# amiga-usb-disk-reader.net
KiCad netlist of a schematic drawn in EAGLE
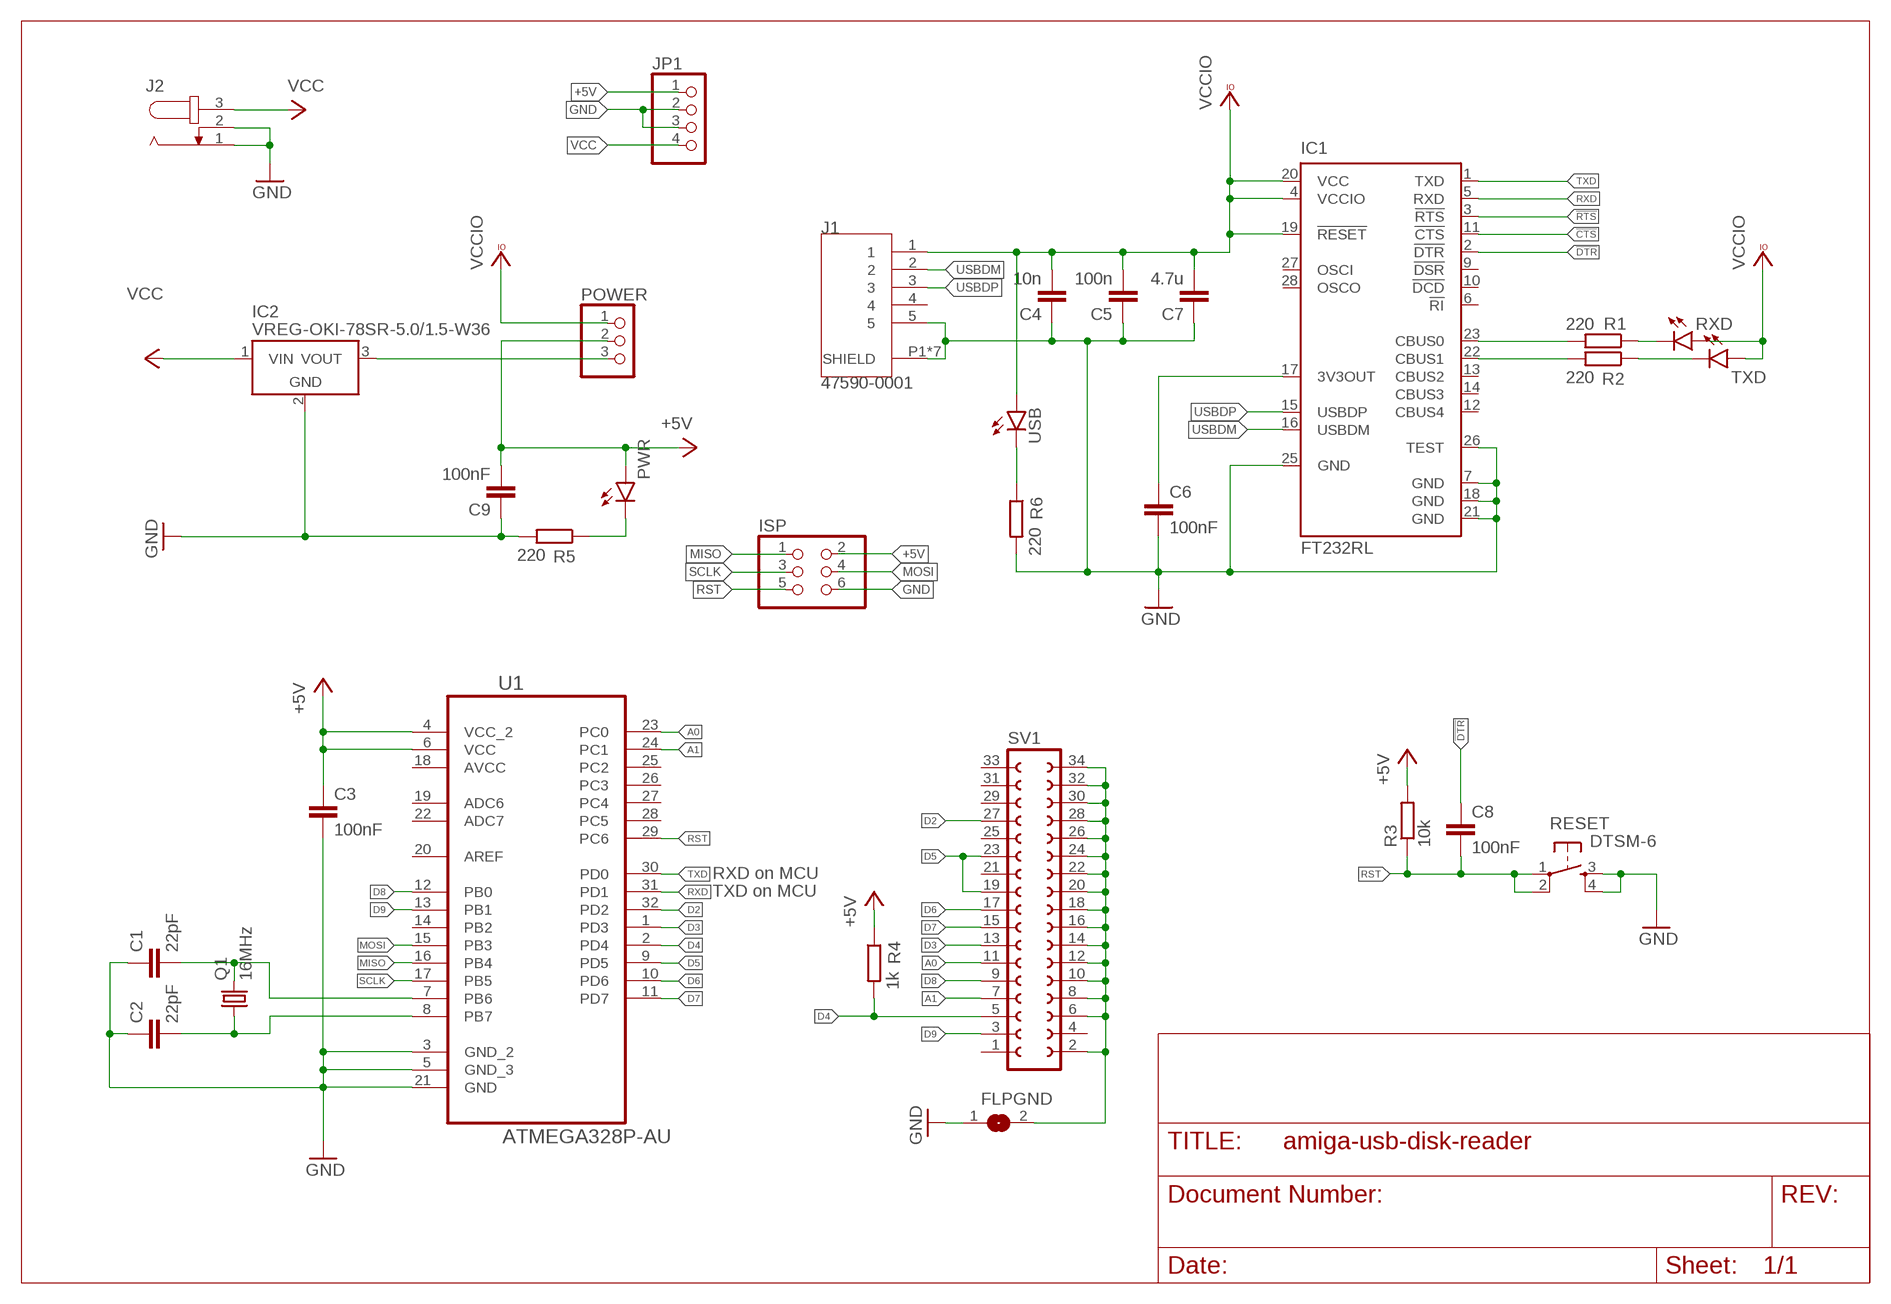
[diagram p0: schematic, sheet 1]

(export (version "E")
  (design (tool "Eeschema 10.0.6"))
  (components
    (comp (ref "C1")
      (value "22pF")
      (footprint "eagle-import:C0805")
      (libsource (lib "eagle-import") (part "C-EUC0805"))
    )
    (comp (ref "C2")
      (value "22pF")
      (footprint "eagle-import:C0805")
      (libsource (lib "eagle-import") (part "C-EUC0805"))
    )
    (comp (ref "C3")
      (value "100nF")
      (footprint "eagle-import:C0805")
      (libsource (lib "eagle-import") (part "C-EUC0805"))
    )
    (comp (ref "C4")
      (value "10n")
      (footprint "eagle-import:C0805")
      (libsource (lib "eagle-import") (part "C-EUC0805"))
    )
    (comp (ref "C5")
      (value "100n")
      (footprint "eagle-import:C0805")
      (libsource (lib "eagle-import") (part "C-EUC0805"))
    )
    (comp (ref "C6")
      (value "100nF")
      (footprint "eagle-import:C0805")
      (libsource (lib "eagle-import") (part "C-EUC0805"))
    )
    (comp (ref "C7")
      (value "4.7u")
      (footprint "eagle-import:C0805")
      (libsource (lib "eagle-import") (part "C-EUC0805"))
    )
    (comp (ref "C8")
      (value "100nF")
      (footprint "eagle-import:C0805")
      (libsource (lib "eagle-import") (part "C-EUC0805"))
    )
    (comp (ref "C9")
      (value "100nF")
      (footprint "eagle-import:C0805")
      (libsource (lib "eagle-import") (part "C-EUC0805"))
    )
    (comp (ref "FLPGND")
      (value "SJ")
      (footprint "eagle-import:SJ")
      (libsource (lib "eagle-import") (part "SJ"))
    )
    (comp (ref "IC1")
      (value "FT232RL")
      (footprint "eagle-import:SSOP28")
      (libsource (lib "eagle-import") (part "FT232RL"))
    )
    (comp (ref "IC2")
      (value "VREG-OKI-78SR-5.0/1.5-W36")
      (footprint "eagle-import:OKI-78SR")
      (libsource (lib "eagle-import") (part "VREG-OKI-78SR-5.0/1.5-W36"))
    )
    (comp (ref "ISP")
      (value "PINHD-2X3")
      (footprint "eagle-import:2X03")
      (libsource (lib "eagle-import") (part "PINHD-2X3"))
    )
    (comp (ref "J1")
      (value "47590-0001")
      (footprint "eagle-import:MOLEX_47590-0001")
      (fields (field (name "MF") "Molex"))
      (libsource (lib "eagle-import") (part "47590-0001"))
    )
    (comp (ref "J2")
      (value "JACK-PLUG0")
      (footprint "eagle-import:SPC4077")
      (libsource (lib "eagle-import") (part "JACK-PLUG0"))
    )
    (comp (ref "JP1")
      (value "PINHD-1X4")
      (footprint "eagle-import:1X04")
      (libsource (lib "eagle-import") (part "PINHD-1X4"))
    )
    (comp (ref "POWER")
      (value "PINHD-1X3")
      (footprint "eagle-import:1X03")
      (libsource (lib "eagle-import") (part "PINHD-1X3"))
    )
    (comp (ref "PWR")
      (value "LEDSML0805")
      (footprint "eagle-import:SML0805")
      (libsource (lib "eagle-import") (part "LEDSML0805"))
    )
    (comp (ref "Q1")
      (value "16MHz")
      (footprint "eagle-import:HC49U70")
      (libsource (lib "eagle-import") (part "CRYSTALHC49U70"))
    )
    (comp (ref "R1")
      (value "220")
      (footprint "eagle-import:R0805")
      (libsource (lib "eagle-import") (part "R-EU_R0805"))
    )
    (comp (ref "R2")
      (value "220")
      (footprint "eagle-import:R0805")
      (libsource (lib "eagle-import") (part "R-EU_R0805"))
    )
    (comp (ref "R3")
      (value "10k")
      (footprint "eagle-import:R0805")
      (libsource (lib "eagle-import") (part "R-EU_R0805"))
    )
    (comp (ref "R4")
      (value "1k")
      (footprint "eagle-import:R0805")
      (libsource (lib "eagle-import") (part "R-EU_R0805"))
    )
    (comp (ref "R5")
      (value "220")
      (footprint "eagle-import:R0805")
      (libsource (lib "eagle-import") (part "R-EU_R0805"))
    )
    (comp (ref "R6")
      (value "220")
      (footprint "eagle-import:R0805")
      (libsource (lib "eagle-import") (part "R-EU_R0805"))
    )
    (comp (ref "RESET")
      (value "DTSM-6")
      (footprint "eagle-import:DTSM-6")
      (libsource (lib "eagle-import") (part "DTSM-6"))
    )
    (comp (ref "RXD")
      (value "LEDSML0805")
      (footprint "eagle-import:SML0805")
      (libsource (lib "eagle-import") (part "LEDSML0805"))
    )
    (comp (ref "SV1")
      (value "FE17-2W")
      (footprint "eagle-import:FE17-2W")
      (libsource (lib "eagle-import") (part "FE17-2W"))
    )
    (comp (ref "TXD")
      (value "LEDSML0805")
      (footprint "eagle-import:SML0805")
      (libsource (lib "eagle-import") (part "LEDSML0805"))
    )
    (comp (ref "U1")
      (value "ATMEGA328P-AU")
      (footprint "eagle-import:QFP80P900X900X120-32N")
      (libsource (lib "eagle-import") (part "ATMEGA328P-AU"))
    )
    (comp (ref "USB")
      (value "LEDSML0805")
      (footprint "eagle-import:SML0805")
      (libsource (lib "eagle-import") (part "LEDSML0805"))
    )
  )
  (nets
    (net (code "1") (name "+5V") (class "Default")
      (node (ref "C3") (pin "1") (pinfunction "1_1") (pintype "passive"))
      (node (ref "C9") (pin "2") (pinfunction "2_2") (pintype "passive"))
      (node (ref "ISP") (pin "2") (pinfunction "2_2") (pintype "passive"))
      (node (ref "JP1") (pin "1") (pinfunction "1_1") (pintype "passive"))
      (node (ref "POWER") (pin "2") (pinfunction "2_2") (pintype "passive"))
      (node (ref "PWR") (pin "A") (pinfunction "A_A") (pintype "passive"))
      (node (ref "R3") (pin "2") (pinfunction "2_2") (pintype "passive"))
      (node (ref "R4") (pin "1") (pinfunction "1_1") (pintype "passive"))
      (node (ref "U1") (pin "4") (pinfunction "VCC_2_4") (pintype "power_in"))
      (node (ref "U1") (pin "6") (pinfunction "VCC_6") (pintype "power_in"))
    )
    (net (code "2") (name "/AVCC") (class "Default")
      (node (ref "U1") (pin "18") (pinfunction "AVCC_18") (pintype "power_in"))
    )
    (net (code "3") (name "/~{CTS}") (class "Default")
      (node (ref "IC1") (pin "11") (pinfunction "~{CTS}_11") (pintype "input"))
    )
    (net (code "4") (name "/~{DTR}") (class "Default")
      (node (ref "C8") (pin "1") (pinfunction "1_1") (pintype "passive"))
      (node (ref "IC1") (pin "2") (pinfunction "~{DTR}_2") (pintype "output"))
    )
    (net (code "5") (name "/~{RTS}") (class "Default")
      (node (ref "IC1") (pin "3") (pinfunction "~{RTS}_3") (pintype "output"))
    )
    (net (code "6") (name "A0") (class "Default")
      (node (ref "SV1") (pin "11") (pinfunction "11_11") (pintype "passive"))
      (node (ref "U1") (pin "23") (pinfunction "PC0_23") (pintype "bidirectional"))
    )
    (net (code "7") (name "A1") (class "Default")
      (node (ref "SV1") (pin "7") (pinfunction "7_7") (pintype "passive"))
      (node (ref "U1") (pin "24") (pinfunction "PC1_24") (pintype "bidirectional"))
    )
    (net (code "8") (name "D2") (class "Default")
      (node (ref "SV1") (pin "27") (pinfunction "27_27") (pintype "passive"))
      (node (ref "U1") (pin "32") (pinfunction "PD2_32") (pintype "bidirectional"))
    )
    (net (code "9") (name "D3") (class "Default")
      (node (ref "SV1") (pin "13") (pinfunction "13_13") (pintype "passive"))
      (node (ref "U1") (pin "1") (pinfunction "PD3_1") (pintype "bidirectional"))
    )
    (net (code "10") (name "D4") (class "Default")
      (node (ref "R4") (pin "2") (pinfunction "2_2") (pintype "passive"))
      (node (ref "SV1") (pin "5") (pinfunction "5_5") (pintype "passive"))
      (node (ref "U1") (pin "2") (pinfunction "PD4_2") (pintype "bidirectional"))
    )
    (net (code "11") (name "D5") (class "Default")
      (node (ref "SV1") (pin "19") (pinfunction "19_19") (pintype "passive"))
      (node (ref "SV1") (pin "23") (pinfunction "23_23") (pintype "passive"))
      (node (ref "U1") (pin "9") (pinfunction "PD5_9") (pintype "bidirectional"))
    )
    (net (code "12") (name "D6") (class "Default")
      (node (ref "SV1") (pin "17") (pinfunction "17_17") (pintype "passive"))
      (node (ref "U1") (pin "10") (pinfunction "PD6_10") (pintype "bidirectional"))
    )
    (net (code "13") (name "D7") (class "Default")
      (node (ref "SV1") (pin "15") (pinfunction "15_15") (pintype "passive"))
      (node (ref "U1") (pin "11") (pinfunction "PD7_11") (pintype "bidirectional"))
    )
    (net (code "14") (name "D8") (class "Default")
      (node (ref "SV1") (pin "9") (pinfunction "9_9") (pintype "passive"))
      (node (ref "U1") (pin "12") (pinfunction "PB0_12") (pintype "bidirectional"))
    )
    (net (code "15") (name "D9") (class "Default")
      (node (ref "SV1") (pin "3") (pinfunction "3_3") (pintype "passive"))
      (node (ref "U1") (pin "13") (pinfunction "PB1_13") (pintype "bidirectional"))
    )
    (net (code "16") (name "GND") (class "Default")
      (node (ref "C1") (pin "1") (pinfunction "1_1") (pintype "passive"))
      (node (ref "C2") (pin "1") (pinfunction "1_1") (pintype "passive"))
      (node (ref "C3") (pin "2") (pinfunction "2_2") (pintype "passive"))
      (node (ref "C4") (pin "1") (pinfunction "1_1") (pintype "passive"))
      (node (ref "C5") (pin "1") (pinfunction "1_1") (pintype "passive"))
      (node (ref "C6") (pin "2") (pinfunction "2_2") (pintype "passive"))
      (node (ref "C7") (pin "1") (pinfunction "1_1") (pintype "passive"))
      (node (ref "C9") (pin "1") (pinfunction "1_1") (pintype "passive"))
      (node (ref "FLPGND") (pin "1") (pinfunction "1_1") (pintype "passive"))
      (node (ref "IC1") (pin "18") (pinfunction "GND_18") (pintype "power_in"))
      (node (ref "IC1") (pin "21") (pinfunction "GND_21") (pintype "power_in"))
      (node (ref "IC1") (pin "25") (pinfunction "GND_25") (pintype "power_in"))
      (node (ref "IC1") (pin "26") (pinfunction "TEST_26") (pintype "input"))
      (node (ref "IC1") (pin "7") (pinfunction "GND_7") (pintype "power_in"))
      (node (ref "IC2") (pin "2") (pinfunction "GND_2") (pintype "power_in"))
      (node (ref "ISP") (pin "6") (pinfunction "6_6") (pintype "passive"))
      (node (ref "J1") (pin "5") (pinfunction "5_5") (pintype "passive"))
      (node (ref "J1") (pin "P1") (pinfunction "SHIELD_P1") (pintype "passive"))
      (node (ref "J1") (pin "P2") (pinfunction "SHIELD_P2") (pintype "passive"))
      (node (ref "J1") (pin "P3") (pinfunction "SHIELD_P3") (pintype "passive"))
      (node (ref "J1") (pin "S1") (pinfunction "SHIELD_S1") (pintype "passive"))
      (node (ref "J1") (pin "S2") (pinfunction "SHIELD_S2") (pintype "passive"))
      (node (ref "J1") (pin "S3") (pinfunction "SHIELD_S3") (pintype "passive"))
      (node (ref "J1") (pin "S4") (pinfunction "SHIELD_S4") (pintype "passive"))
      (node (ref "J2") (pin "1") (pinfunction "1_1") (pintype "passive"))
      (node (ref "J2") (pin "2") (pinfunction "2_2") (pintype "passive"))
      (node (ref "JP1") (pin "2") (pinfunction "2_2") (pintype "passive"))
      (node (ref "JP1") (pin "3") (pinfunction "3_3") (pintype "passive"))
      (node (ref "R5") (pin "2") (pinfunction "2_2") (pintype "passive"))
      (node (ref "R6") (pin "2") (pinfunction "2_2") (pintype "passive"))
      (node (ref "RESET") (pin "3") (pinfunction "3_3") (pintype "passive"))
      (node (ref "RESET") (pin "4") (pinfunction "4_4") (pintype "passive"))
      (node (ref "U1") (pin "21") (pinfunction "GND_21") (pintype "passive"))
      (node (ref "U1") (pin "3") (pinfunction "GND_2_3") (pintype "passive"))
      (node (ref "U1") (pin "5") (pinfunction "GND_3_5") (pintype "passive"))
    )
    (net (code "17") (name "MISO") (class "Default")
      (node (ref "ISP") (pin "1") (pinfunction "1_1") (pintype "passive"))
      (node (ref "U1") (pin "16") (pinfunction "PB4_16") (pintype "bidirectional"))
    )
    (net (code "18") (name "MOSI") (class "Default")
      (node (ref "ISP") (pin "4") (pinfunction "4_4") (pintype "passive"))
      (node (ref "U1") (pin "15") (pinfunction "PB3_15") (pintype "bidirectional"))
    )
    (net (code "19") (name "Net-(FLPGND-Pad2)") (class "Default")
      (node (ref "FLPGND") (pin "2") (pinfunction "2_2") (pintype "passive"))
      (node (ref "SV1") (pin "10") (pinfunction "10_10") (pintype "passive"))
      (node (ref "SV1") (pin "12") (pinfunction "12_12") (pintype "passive"))
      (node (ref "SV1") (pin "14") (pinfunction "14_14") (pintype "passive"))
      (node (ref "SV1") (pin "16") (pinfunction "16_16") (pintype "passive"))
      (node (ref "SV1") (pin "18") (pinfunction "18_18") (pintype "passive"))
      (node (ref "SV1") (pin "2") (pinfunction "2_2") (pintype "passive"))
      (node (ref "SV1") (pin "20") (pinfunction "20_20") (pintype "passive"))
      (node (ref "SV1") (pin "22") (pinfunction "22_22") (pintype "passive"))
      (node (ref "SV1") (pin "24") (pinfunction "24_24") (pintype "passive"))
      (node (ref "SV1") (pin "26") (pinfunction "26_26") (pintype "passive"))
      (node (ref "SV1") (pin "28") (pinfunction "28_28") (pintype "passive"))
      (node (ref "SV1") (pin "30") (pinfunction "30_30") (pintype "passive"))
      (node (ref "SV1") (pin "32") (pinfunction "32_32") (pintype "passive"))
      (node (ref "SV1") (pin "34") (pinfunction "34_34") (pintype "passive"))
      (node (ref "SV1") (pin "6") (pinfunction "6_6") (pintype "passive"))
      (node (ref "SV1") (pin "8") (pinfunction "8_8") (pintype "passive"))
    )
    (net (code "20") (name "Net-(IC1-3V3OUT)") (class "Default")
      (node (ref "C6") (pin "1") (pinfunction "1_1") (pintype "passive"))
      (node (ref "IC1") (pin "17") (pinfunction "3V3OUT_17") (pintype "output"))
    )
    (net (code "21") (name "Net-(IC1-CBUS0)") (class "Default")
      (node (ref "IC1") (pin "23") (pinfunction "CBUS0_23") (pintype "bidirectional"))
      (node (ref "R1") (pin "2") (pinfunction "2_2") (pintype "passive"))
    )
    (net (code "22") (name "Net-(IC1-CBUS1)") (class "Default")
      (node (ref "IC1") (pin "22") (pinfunction "CBUS1_22") (pintype "bidirectional"))
      (node (ref "R2") (pin "2") (pinfunction "2_2") (pintype "passive"))
    )
    (net (code "23") (name "Net-(IC2-VOUT)") (class "Default")
      (node (ref "IC2") (pin "3") (pinfunction "VOUT_3") (pintype "power_in"))
      (node (ref "POWER") (pin "3") (pinfunction "3_3") (pintype "passive"))
    )
    (net (code "24") (name "Net-(PWR-PadC)") (class "Default")
      (node (ref "PWR") (pin "C") (pinfunction "C_C") (pintype "passive"))
      (node (ref "R5") (pin "1") (pinfunction "1_1") (pintype "passive"))
    )
    (net (code "25") (name "Net-(R1-Pad1)") (class "Default")
      (node (ref "R1") (pin "1") (pinfunction "1_1") (pintype "passive"))
      (node (ref "RXD") (pin "C") (pinfunction "C_C") (pintype "passive"))
    )
    (net (code "26") (name "Net-(R2-Pad1)") (class "Default")
      (node (ref "R2") (pin "1") (pinfunction "1_1") (pintype "passive"))
      (node (ref "TXD") (pin "C") (pinfunction "C_C") (pintype "passive"))
    )
    (net (code "27") (name "Net-(R6-Pad1)") (class "Default")
      (node (ref "R6") (pin "1") (pinfunction "1_1") (pintype "passive"))
      (node (ref "USB") (pin "C") (pinfunction "C_C") (pintype "passive"))
    )
    (net (code "28") (name "Net-(U1-PB6)") (class "Default")
      (node (ref "C1") (pin "2") (pinfunction "2_2") (pintype "passive"))
      (node (ref "Q1") (pin "2") (pinfunction "2_2") (pintype "passive"))
      (node (ref "U1") (pin "7") (pinfunction "PB6_7") (pintype "bidirectional"))
    )
    (net (code "29") (name "Net-(U1-PB7)") (class "Default")
      (node (ref "C2") (pin "2") (pinfunction "2_2") (pintype "passive"))
      (node (ref "Q1") (pin "1") (pinfunction "1_1") (pintype "passive"))
      (node (ref "U1") (pin "8") (pinfunction "PB7_8") (pintype "bidirectional"))
    )
    (net (code "30") (name "RST") (class "Default")
      (node (ref "C8") (pin "2") (pinfunction "2_2") (pintype "passive"))
      (node (ref "ISP") (pin "5") (pinfunction "5_5") (pintype "passive"))
      (node (ref "R3") (pin "1") (pinfunction "1_1") (pintype "passive"))
      (node (ref "RESET") (pin "1") (pinfunction "1_1") (pintype "passive"))
      (node (ref "RESET") (pin "2") (pinfunction "2_2") (pintype "passive"))
    )
    (net (code "31") (name "RXD") (class "Default")
      (node (ref "IC1") (pin "5") (pinfunction "RXD_5") (pintype "input"))
      (node (ref "U1") (pin "31") (pinfunction "PD1_31") (pintype "bidirectional"))
    )
    (net (code "32") (name "SCLK") (class "Default")
      (node (ref "ISP") (pin "3") (pinfunction "3_3") (pintype "passive"))
      (node (ref "U1") (pin "17") (pinfunction "PB5_17") (pintype "bidirectional"))
    )
    (net (code "33") (name "TXD") (class "Default")
      (node (ref "IC1") (pin "1") (pinfunction "TXD_1") (pintype "output"))
      (node (ref "U1") (pin "30") (pinfunction "PD0_30") (pintype "bidirectional"))
    )
    (net (code "34") (name "USBDM") (class "Default")
      (node (ref "IC1") (pin "16") (pinfunction "USBDM_16") (pintype "bidirectional"))
      (node (ref "J1") (pin "2") (pinfunction "2_2") (pintype "passive"))
    )
    (net (code "35") (name "USBDP") (class "Default")
      (node (ref "IC1") (pin "15") (pinfunction "USBDP_15") (pintype "bidirectional"))
      (node (ref "J1") (pin "3") (pinfunction "3_3") (pintype "passive"))
    )
    (net (code "36") (name "VCC") (class "Default")
      (node (ref "IC2") (pin "1") (pinfunction "VIN_1") (pintype "power_in"))
      (node (ref "J2") (pin "3") (pinfunction "3_3") (pintype "passive"))
      (node (ref "JP1") (pin "4") (pinfunction "4_4") (pintype "passive"))
    )
    (net (code "37") (name "VCCIO") (class "Default")
      (node (ref "C4") (pin "2") (pinfunction "2_2") (pintype "passive"))
      (node (ref "C5") (pin "2") (pinfunction "2_2") (pintype "passive"))
      (node (ref "C7") (pin "2") (pinfunction "2_2") (pintype "passive"))
      (node (ref "IC1") (pin "19") (pinfunction "~{RESET}_19") (pintype "input"))
      (node (ref "IC1") (pin "20") (pinfunction "VCC_20") (pintype "power_in"))
      (node (ref "IC1") (pin "4") (pinfunction "VCCIO_4") (pintype "power_in"))
      (node (ref "J1") (pin "1") (pinfunction "1_1") (pintype "passive"))
      (node (ref "POWER") (pin "1") (pinfunction "1_1") (pintype "passive"))
      (node (ref "RXD") (pin "A") (pinfunction "A_A") (pintype "passive"))
      (node (ref "TXD") (pin "A") (pinfunction "A_A") (pintype "passive"))
      (node (ref "USB") (pin "A") (pinfunction "A_A") (pintype "passive"))
    )
    (net (code "38") (name "unconnected-(IC1-CBUS2-Pad13)") (class "Default")
      (node (ref "IC1") (pin "13") (pinfunction "CBUS2_13") (pintype "bidirectional"))
    )
    (net (code "39") (name "unconnected-(IC1-CBUS3-Pad14)") (class "Default")
      (node (ref "IC1") (pin "14") (pinfunction "CBUS3_14") (pintype "bidirectional"))
    )
    (net (code "40") (name "unconnected-(IC1-CBUS4-Pad12)") (class "Default")
      (node (ref "IC1") (pin "12") (pinfunction "CBUS4_12") (pintype "bidirectional"))
    )
    (net (code "41") (name "unconnected-(IC1-OSCI-Pad27)") (class "Default")
      (node (ref "IC1") (pin "27") (pinfunction "OSCI_27") (pintype "input"))
    )
    (net (code "42") (name "unconnected-(IC1-OSCO-Pad28)") (class "Default")
      (node (ref "IC1") (pin "28") (pinfunction "OSCO_28") (pintype "output"))
    )
    (net (code "43") (name "unconnected-(IC1-~{DCD}-Pad10)") (class "Default")
      (node (ref "IC1") (pin "10") (pinfunction "~{DCD}_10") (pintype "input"))
    )
    (net (code "44") (name "unconnected-(IC1-~{DSR}-Pad9)") (class "Default")
      (node (ref "IC1") (pin "9") (pinfunction "~{DSR}_9") (pintype "input"))
    )
    (net (code "45") (name "unconnected-(IC1-~{RI}-Pad6)") (class "Default")
      (node (ref "IC1") (pin "6") (pinfunction "~{RI}_6") (pintype "input"))
    )
    (net (code "46") (name "unconnected-(J1-Pad4)") (class "Default")
      (node (ref "J1") (pin "4") (pinfunction "4_4") (pintype "passive"))
    )
    (net (code "47") (name "unconnected-(SV1-Pad1)") (class "Default")
      (node (ref "SV1") (pin "1") (pinfunction "1_1") (pintype "passive"))
    )
    (net (code "48") (name "unconnected-(SV1-Pad4)") (class "Default")
      (node (ref "SV1") (pin "4") (pinfunction "4_4") (pintype "passive"))
    )
    (net (code "49") (name "unconnected-(SV1-Pad21)") (class "Default")
      (node (ref "SV1") (pin "21") (pinfunction "21_21") (pintype "passive"))
    )
    (net (code "50") (name "unconnected-(SV1-Pad25)") (class "Default")
      (node (ref "SV1") (pin "25") (pinfunction "25_25") (pintype "passive"))
    )
    (net (code "51") (name "unconnected-(SV1-Pad29)") (class "Default")
      (node (ref "SV1") (pin "29") (pinfunction "29_29") (pintype "passive"))
    )
    (net (code "52") (name "unconnected-(SV1-Pad31)") (class "Default")
      (node (ref "SV1") (pin "31") (pinfunction "31_31") (pintype "passive"))
    )
    (net (code "53") (name "unconnected-(SV1-Pad33)") (class "Default")
      (node (ref "SV1") (pin "33") (pinfunction "33_33") (pintype "passive"))
    )
    (net (code "54") (name "unconnected-(U1-ADC6-Pad19)") (class "Default")
      (node (ref "U1") (pin "19") (pinfunction "ADC6_19") (pintype "input"))
    )
    (net (code "55") (name "unconnected-(U1-ADC7-Pad22)") (class "Default")
      (node (ref "U1") (pin "22") (pinfunction "ADC7_22") (pintype "input"))
    )
    (net (code "56") (name "unconnected-(U1-AREF-Pad20)") (class "Default")
      (node (ref "U1") (pin "20") (pinfunction "AREF_20") (pintype "input"))
    )
    (net (code "57") (name "unconnected-(U1-PB2-Pad14)") (class "Default")
      (node (ref "U1") (pin "14") (pinfunction "PB2_14") (pintype "bidirectional"))
    )
    (net (code "58") (name "unconnected-(U1-PC2-Pad25)") (class "Default")
      (node (ref "U1") (pin "25") (pinfunction "PC2_25") (pintype "bidirectional"))
    )
    (net (code "59") (name "unconnected-(U1-PC3-Pad26)") (class "Default")
      (node (ref "U1") (pin "26") (pinfunction "PC3_26") (pintype "bidirectional"))
    )
    (net (code "60") (name "unconnected-(U1-PC4-Pad27)") (class "Default")
      (node (ref "U1") (pin "27") (pinfunction "PC4_27") (pintype "bidirectional"))
    )
    (net (code "61") (name "unconnected-(U1-PC5-Pad28)") (class "Default")
      (node (ref "U1") (pin "28") (pinfunction "PC5_28") (pintype "bidirectional"))
    )
    (net (code "62") (name "unconnected-(U1-PC6-Pad29)") (class "Default")
      (node (ref "U1") (pin "29") (pinfunction "PC6_29") (pintype "bidirectional"))
    )
  )
)
